# T-STorM32_motor_v251E-sq_Encoder.net
KiCad netlist of a schematic drawn in EAGLE
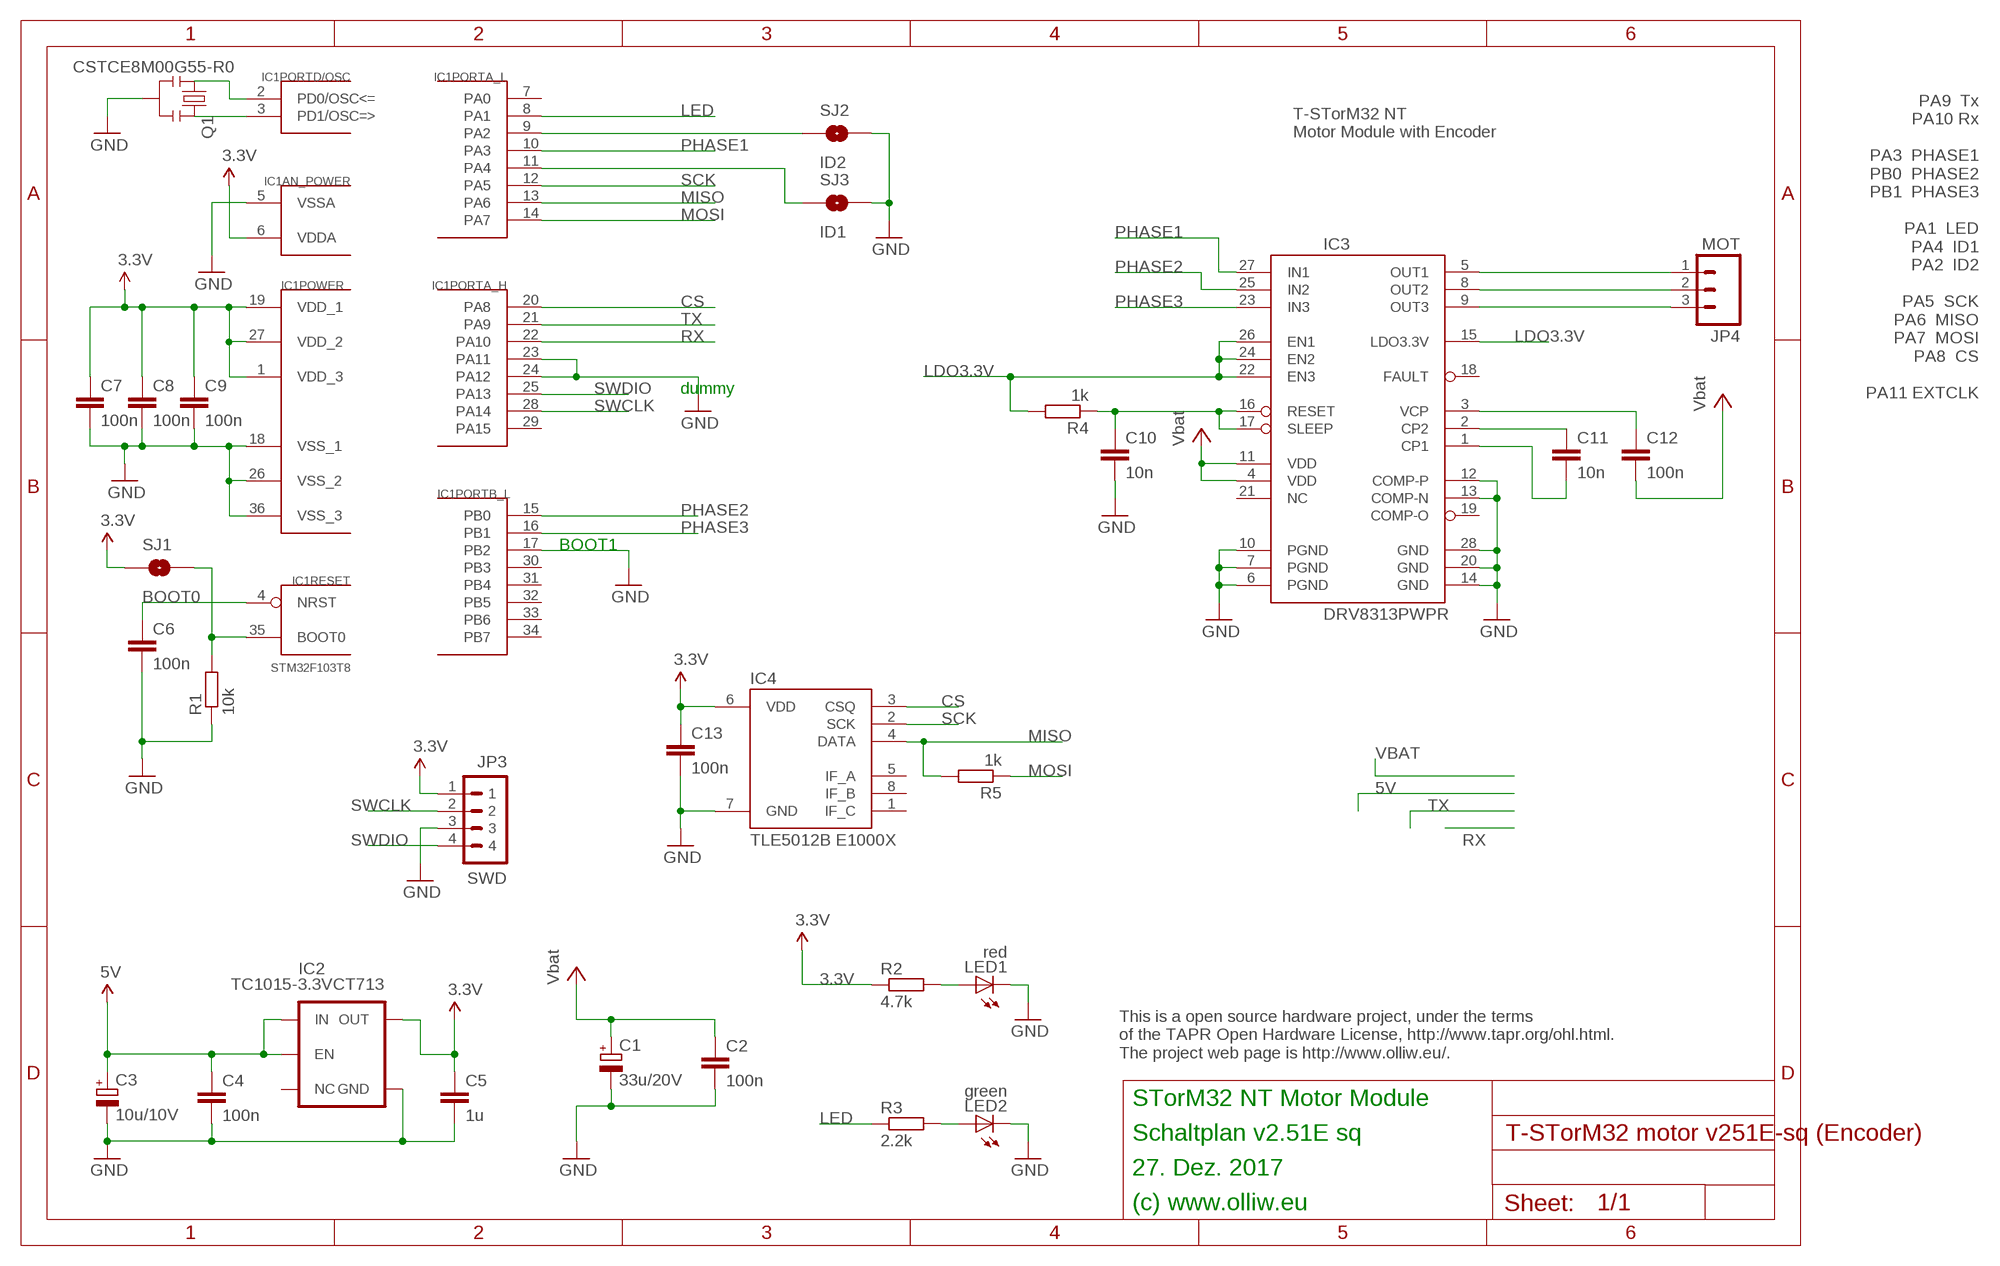
[diagram p0: schematic, sheet 1]

(export (version "E")
  (design (tool "Eeschema 10.0.6"))
  (components
    (comp (ref "C1")
      (value "33u/20V")
      (footprint "eagle-import:SMC_C")
      (libsource (lib "eagle-import") (part "CPOL-EUSMCC"))
    )
    (comp (ref "C2")
      (value "100n")
      (footprint "eagle-import:C0603")
      (libsource (lib "eagle-import") (part "C-EUC0603"))
    )
    (comp (ref "C3")
      (value "10u/10V")
      (footprint "eagle-import:SMC_B")
      (libsource (lib "eagle-import") (part "CPOL-EUSMCB"))
    )
    (comp (ref "C4")
      (value "100n")
      (footprint "eagle-import:C0603")
      (libsource (lib "eagle-import") (part "C-EUC0603"))
    )
    (comp (ref "C5")
      (value "1u")
      (footprint "eagle-import:C0603")
      (libsource (lib "eagle-import") (part "C-EUC0603"))
    )
    (comp (ref "C6")
      (value "100n")
      (footprint "eagle-import:C0603")
      (libsource (lib "eagle-import") (part "C-EUC0603"))
    )
    (comp (ref "C7")
      (value "100n")
      (footprint "eagle-import:C0603")
      (libsource (lib "eagle-import") (part "C-EUC0603"))
    )
    (comp (ref "C8")
      (value "100n")
      (footprint "eagle-import:C0603")
      (libsource (lib "eagle-import") (part "C-EUC0603"))
    )
    (comp (ref "C9")
      (value "100n")
      (footprint "eagle-import:C0603")
      (libsource (lib "eagle-import") (part "C-EUC0603"))
    )
    (comp (ref "C10")
      (value "10n")
      (footprint "eagle-import:C0603")
      (libsource (lib "eagle-import") (part "C-EUC0603"))
    )
    (comp (ref "C11")
      (value "10n")
      (footprint "eagle-import:C0603")
      (libsource (lib "eagle-import") (part "C-EUC0603"))
    )
    (comp (ref "C12")
      (value "100n")
      (footprint "eagle-import:C0603")
      (libsource (lib "eagle-import") (part "C-EUC0603"))
    )
    (comp (ref "C13")
      (value "100n")
      (footprint "eagle-import:C0603")
      (libsource (lib "eagle-import") (part "C-EUC0603"))
    )
    (comp (ref "IC1")
      (value "STM32F103T8")
      (footprint "eagle-import:VFQFPN36")
      (libsource (lib "eagle-import") (part "STM32F10XTXU6"))
    )
    (comp (ref "IC2")
      (value "TC1015-3.3VCT713")
      (footprint "eagle-import:SOT23-5")
      (libsource (lib "eagle-import") (part "V_REG_TPS76433SOT23-5"))
    )
    (comp (ref "IC3")
      (value "DRV8313PWPR")
      (footprint "eagle-import:HTSSOP28")
      (libsource (lib "eagle-import") (part "DRV8313"))
    )
    (comp (ref "IC4")
      (value "TLE5012B E1000X")
      (footprint "eagle-import:SO08")
      (libsource (lib "eagle-import") (part "TLE5012B"))
    )
    (comp (ref "JP3")
      (value "SWD")
      (footprint "eagle-import:4X1_1P27_OCT_BILEX")
      (libsource (lib "eagle-import") (part "P4X1_1P27-OCT_BILEX"))
    )
    (comp (ref "JP4")
      (value "MOT")
      (footprint "eagle-import:1X03_NO_SILK")
      (libsource (lib "eagle-import") (part "M031X03_NO_SILK"))
    )
    (comp (ref "LED1")
      (value "red")
      (footprint "eagle-import:CHIPLED_0603")
      (libsource (lib "eagle-import") (part "LEDCHIPLED_0603"))
    )
    (comp (ref "LED2")
      (value "green")
      (footprint "eagle-import:CHIPLED_0603")
      (libsource (lib "eagle-import") (part "LEDCHIPLED_0603"))
    )
    (comp (ref "Q1")
      (value "CSTCE8M00G55-R0")
      (footprint "eagle-import:RESONATOR-SMD")
      (libsource (lib "eagle-import") (part "RESONATORSMD"))
    )
    (comp (ref "R1")
      (value "10k")
      (footprint "eagle-import:R0603")
      (libsource (lib "eagle-import") (part "R-EU_R0603"))
    )
    (comp (ref "R2")
      (value "4.7k")
      (footprint "eagle-import:R0603")
      (libsource (lib "eagle-import") (part "R-EU_R0603"))
    )
    (comp (ref "R3")
      (value "2.2k")
      (footprint "eagle-import:R0603")
      (libsource (lib "eagle-import") (part "R-EU_R0603"))
    )
    (comp (ref "R4")
      (value "1k")
      (footprint "eagle-import:R0603")
      (libsource (lib "eagle-import") (part "R-EU_R0603"))
    )
    (comp (ref "R5")
      (value "1k")
      (footprint "eagle-import:R0603")
      (libsource (lib "eagle-import") (part "R-EU_R0603"))
    )
    (comp (ref "SJ1")
      (value "BOOT0")
      (footprint "eagle-import:SJ_2S-NO")
      (libsource (lib "eagle-import") (part "SOLDERJUMPERNO"))
    )
    (comp (ref "SJ2")
      (value "ID2")
      (footprint "eagle-import:SJ_2S-NO")
      (libsource (lib "eagle-import") (part "SOLDERJUMPERNO"))
    )
    (comp (ref "SJ3")
      (value "ID1")
      (footprint "eagle-import:SJ_2S-NO")
      (libsource (lib "eagle-import") (part "SOLDERJUMPERNO"))
    )
  )
  (nets
    (net (code "1") (name "/CS") (class "Default")
      (node (ref "IC1") (pin "20") (pinfunction "PA8_20") (pintype "bidirectional"))
      (node (ref "IC4") (pin "3") (pinfunction "CSQ_3") (pintype "input"))
    )
    (net (code "2") (name "/LDO3.3V") (class "Default")
      (node (ref "IC3") (pin "15") (pinfunction "LDO3.3V_15") (pintype "output"))
      (node (ref "IC3") (pin "22") (pinfunction "EN3_22") (pintype "input"))
      (node (ref "IC3") (pin "24") (pinfunction "EN2_24") (pintype "input"))
      (node (ref "IC3") (pin "26") (pinfunction "EN1_26") (pintype "input"))
      (node (ref "R4") (pin "2") (pinfunction "2_2") (pintype "passive"))
    )
    (net (code "3") (name "/LED") (class "Default")
      (node (ref "IC1") (pin "8") (pinfunction "PA1_8") (pintype "bidirectional"))
      (node (ref "R3") (pin "1") (pinfunction "1_1") (pintype "passive"))
    )
    (net (code "4") (name "/MISO") (class "Default")
      (node (ref "IC1") (pin "13") (pinfunction "PA6_13") (pintype "bidirectional"))
      (node (ref "IC4") (pin "4") (pinfunction "DATA_4") (pintype "bidirectional"))
      (node (ref "R5") (pin "2") (pinfunction "2_2") (pintype "passive"))
    )
    (net (code "5") (name "/MOSI") (class "Default")
      (node (ref "IC1") (pin "14") (pinfunction "PA7_14") (pintype "bidirectional"))
      (node (ref "R5") (pin "1") (pinfunction "1_1") (pintype "passive"))
    )
    (net (code "6") (name "/PHASE1") (class "Default")
      (node (ref "IC1") (pin "10") (pinfunction "PA3_10") (pintype "bidirectional"))
      (node (ref "IC3") (pin "27") (pinfunction "IN1_27") (pintype "input"))
    )
    (net (code "7") (name "/PHASE2") (class "Default")
      (node (ref "IC1") (pin "15") (pinfunction "PB0_15") (pintype "bidirectional"))
      (node (ref "IC3") (pin "25") (pinfunction "IN2_25") (pintype "input"))
    )
    (net (code "8") (name "/PHASE3") (class "Default")
      (node (ref "IC1") (pin "16") (pinfunction "PB1_16") (pintype "bidirectional"))
      (node (ref "IC3") (pin "23") (pinfunction "IN3_23") (pintype "input"))
    )
    (net (code "9") (name "/RX") (class "Default")
      (node (ref "IC1") (pin "22") (pinfunction "PA10_22") (pintype "bidirectional"))
    )
    (net (code "10") (name "/SCK") (class "Default")
      (node (ref "IC1") (pin "12") (pinfunction "PA5_12") (pintype "bidirectional"))
      (node (ref "IC4") (pin "2") (pinfunction "SCK_2") (pintype "input"))
    )
    (net (code "11") (name "/SWCLK") (class "Default")
      (node (ref "IC1") (pin "28") (pinfunction "PA14_28") (pintype "bidirectional"))
      (node (ref "JP3") (pin "2") (pinfunction "2_2") (pintype "passive"))
    )
    (net (code "12") (name "/SWDIO") (class "Default")
      (node (ref "IC1") (pin "25") (pinfunction "PA13_25") (pintype "bidirectional"))
      (node (ref "JP3") (pin "4") (pinfunction "4_4") (pintype "passive"))
    )
    (net (code "13") (name "/TX") (class "Default")
      (node (ref "IC1") (pin "21") (pinfunction "PA9_21") (pintype "bidirectional"))
    )
    (net (code "14") (name "3.3V") (class "Default")
      (node (ref "C13") (pin "1") (pinfunction "1_1") (pintype "passive"))
      (node (ref "C5") (pin "1") (pinfunction "1_1") (pintype "passive"))
      (node (ref "C7") (pin "1") (pinfunction "1_1") (pintype "passive"))
      (node (ref "C8") (pin "1") (pinfunction "1_1") (pintype "passive"))
      (node (ref "C9") (pin "1") (pinfunction "1_1") (pintype "passive"))
      (node (ref "IC1") (pin "1") (pinfunction "VDD_3_1") (pintype "power_in"))
      (node (ref "IC1") (pin "19") (pinfunction "VDD_1_19") (pintype "power_in"))
      (node (ref "IC1") (pin "27") (pinfunction "VDD_2_27") (pintype "power_in"))
      (node (ref "IC1") (pin "6") (pinfunction "VDDA_6") (pintype "power_in"))
      (node (ref "IC2") (pin "5") (pinfunction "OUT_5") (pintype "passive"))
      (node (ref "IC4") (pin "6") (pinfunction "VDD_6") (pintype "power_in"))
      (node (ref "JP3") (pin "1") (pinfunction "1_1") (pintype "passive"))
      (node (ref "R2") (pin "1") (pinfunction "1_1") (pintype "passive"))
      (node (ref "SJ1") (pin "1") (pinfunction "1_1") (pintype "passive"))
    )
    (net (code "15") (name "5V") (class "Default")
      (node (ref "C3") (pin "+") (pinfunction "+_+") (pintype "passive"))
      (node (ref "C4") (pin "1") (pinfunction "1_1") (pintype "passive"))
      (node (ref "IC2") (pin "1") (pinfunction "IN_1") (pintype "input"))
      (node (ref "IC2") (pin "3") (pinfunction "EN_3") (pintype "input"))
    )
    (net (code "16") (name "GND") (class "Default")
      (node (ref "C1") (pin "-") (pinfunction "-_-") (pintype "passive"))
      (node (ref "C10") (pin "2") (pinfunction "2_2") (pintype "passive"))
      (node (ref "C13") (pin "2") (pinfunction "2_2") (pintype "passive"))
      (node (ref "C2") (pin "2") (pinfunction "2_2") (pintype "passive"))
      (node (ref "C3") (pin "-") (pinfunction "-_-") (pintype "passive"))
      (node (ref "C4") (pin "2") (pinfunction "2_2") (pintype "passive"))
      (node (ref "C5") (pin "2") (pinfunction "2_2") (pintype "passive"))
      (node (ref "C6") (pin "2") (pinfunction "2_2") (pintype "passive"))
      (node (ref "C7") (pin "2") (pinfunction "2_2") (pintype "passive"))
      (node (ref "C8") (pin "2") (pinfunction "2_2") (pintype "passive"))
      (node (ref "C9") (pin "2") (pinfunction "2_2") (pintype "passive"))
      (node (ref "IC1") (pin "17") (pinfunction "PB2_17") (pintype "bidirectional"))
      (node (ref "IC1") (pin "18") (pinfunction "VSS_1_18") (pintype "power_in"))
      (node (ref "IC1") (pin "23") (pinfunction "PA11_23") (pintype "bidirectional"))
      (node (ref "IC1") (pin "24") (pinfunction "PA12_24") (pintype "bidirectional"))
      (node (ref "IC1") (pin "26") (pinfunction "VSS_2_26") (pintype "power_in"))
      (node (ref "IC1") (pin "36") (pinfunction "VSS_3_36") (pintype "power_in"))
      (node (ref "IC1") (pin "5") (pinfunction "VSSA_5") (pintype "power_in"))
      (node (ref "IC2") (pin "2") (pinfunction "GND_2") (pintype "input"))
      (node (ref "IC3") (pin "10") (pinfunction "PGND_10") (pintype "power_in"))
      (node (ref "IC3") (pin "12") (pinfunction "COMP-P_12") (pintype "input"))
      (node (ref "IC3") (pin "13") (pinfunction "COMP-N_13") (pintype "input"))
      (node (ref "IC3") (pin "14") (pinfunction "GND_14") (pintype "power_in"))
      (node (ref "IC3") (pin "20") (pinfunction "GND_20") (pintype "power_in"))
      (node (ref "IC3") (pin "28") (pinfunction "GND_28") (pintype "power_in"))
      (node (ref "IC3") (pin "6") (pinfunction "PGND_6") (pintype "power_in"))
      (node (ref "IC3") (pin "7") (pinfunction "PGND_7") (pintype "power_in"))
      (node (ref "IC4") (pin "7") (pinfunction "GND_7") (pintype "power_in"))
      (node (ref "JP3") (pin "3") (pinfunction "3_3") (pintype "passive"))
      (node (ref "LED1") (pin "C") (pinfunction "C_C") (pintype "passive"))
      (node (ref "LED2") (pin "C") (pinfunction "C_C") (pintype "passive"))
      (node (ref "Q1") (pin "2") (pinfunction "2_2") (pintype "passive"))
      (node (ref "R1") (pin "1") (pinfunction "1_1") (pintype "passive"))
      (node (ref "SJ2") (pin "2") (pinfunction "2_2") (pintype "passive"))
      (node (ref "SJ3") (pin "2") (pinfunction "2_2") (pintype "passive"))
    )
    (net (code "17") (name "Net-(IC1C-PA2)") (class "Default")
      (node (ref "IC1") (pin "9") (pinfunction "PA2_9") (pintype "bidirectional"))
      (node (ref "SJ2") (pin "1") (pinfunction "1_1") (pintype "passive"))
    )
    (net (code "18") (name "Net-(IC1C-PA4)") (class "Default")
      (node (ref "IC1") (pin "11") (pinfunction "PA4_11") (pintype "bidirectional"))
      (node (ref "SJ3") (pin "1") (pinfunction "1_1") (pintype "passive"))
    )
    (net (code "19") (name "Net-(IC1E-PD0{slash}OSC<=)") (class "Default")
      (node (ref "IC1") (pin "2") (pinfunction "PD0/OSC<=_2") (pintype "bidirectional"))
      (node (ref "Q1") (pin "1") (pinfunction "1_1") (pintype "passive"))
    )
    (net (code "20") (name "Net-(IC1E-PD1{slash}OSC=>)") (class "Default")
      (node (ref "IC1") (pin "3") (pinfunction "PD1/OSC=>_3") (pintype "bidirectional"))
      (node (ref "Q1") (pin "3") (pinfunction "3_3") (pintype "passive"))
    )
    (net (code "21") (name "Net-(IC1G-BOOT0)") (class "Default")
      (node (ref "IC1") (pin "35") (pinfunction "BOOT0_35") (pintype "input"))
      (node (ref "R1") (pin "2") (pinfunction "2_2") (pintype "passive"))
      (node (ref "SJ1") (pin "2") (pinfunction "2_2") (pintype "passive"))
    )
    (net (code "22") (name "Net-(IC1G-NRST)") (class "Default")
      (node (ref "C6") (pin "1") (pinfunction "1_1") (pintype "passive"))
      (node (ref "IC1") (pin "4") (pinfunction "NRST_4") (pintype "input"))
    )
    (net (code "23") (name "Net-(IC3-CP1)") (class "Default")
      (node (ref "C11") (pin "2") (pinfunction "2_2") (pintype "passive"))
      (node (ref "IC3") (pin "1") (pinfunction "CP1_1") (pintype "bidirectional"))
    )
    (net (code "24") (name "Net-(IC3-CP2)") (class "Default")
      (node (ref "C11") (pin "1") (pinfunction "1_1") (pintype "passive"))
      (node (ref "IC3") (pin "2") (pinfunction "CP2_2") (pintype "bidirectional"))
    )
    (net (code "25") (name "Net-(IC3-OUT1)") (class "Default")
      (node (ref "IC3") (pin "5") (pinfunction "OUT1_5") (pintype "output"))
      (node (ref "JP4") (pin "1") (pinfunction "1_1") (pintype "passive"))
    )
    (net (code "26") (name "Net-(IC3-OUT2)") (class "Default")
      (node (ref "IC3") (pin "8") (pinfunction "OUT2_8") (pintype "output"))
      (node (ref "JP4") (pin "2") (pinfunction "2_2") (pintype "passive"))
    )
    (net (code "27") (name "Net-(IC3-OUT3)") (class "Default")
      (node (ref "IC3") (pin "9") (pinfunction "OUT3_9") (pintype "output"))
      (node (ref "JP4") (pin "3") (pinfunction "3_3") (pintype "passive"))
    )
    (net (code "28") (name "Net-(IC3-RESET)") (class "Default")
      (node (ref "C10") (pin "1") (pinfunction "1_1") (pintype "passive"))
      (node (ref "IC3") (pin "16") (pinfunction "RESET_16") (pintype "input"))
      (node (ref "IC3") (pin "17") (pinfunction "SLEEP_17") (pintype "input"))
      (node (ref "R4") (pin "1") (pinfunction "1_1") (pintype "passive"))
    )
    (net (code "29") (name "Net-(IC3-VCP)") (class "Default")
      (node (ref "C12") (pin "1") (pinfunction "1_1") (pintype "passive"))
      (node (ref "IC3") (pin "3") (pinfunction "VCP_3") (pintype "bidirectional"))
    )
    (net (code "30") (name "Net-(LED1-PadA)") (class "Default")
      (node (ref "LED1") (pin "A") (pinfunction "A_A") (pintype "passive"))
      (node (ref "R2") (pin "2") (pinfunction "2_2") (pintype "passive"))
    )
    (net (code "31") (name "Net-(LED2-PadA)") (class "Default")
      (node (ref "LED2") (pin "A") (pinfunction "A_A") (pintype "passive"))
      (node (ref "R3") (pin "2") (pinfunction "2_2") (pintype "passive"))
    )
    (net (code "32") (name "Vbat") (class "Default")
      (node (ref "C1") (pin "+") (pinfunction "+_+") (pintype "passive"))
      (node (ref "C12") (pin "2") (pinfunction "2_2") (pintype "passive"))
      (node (ref "C2") (pin "1") (pinfunction "1_1") (pintype "passive"))
      (node (ref "IC3") (pin "11") (pinfunction "VDD_11") (pintype "power_in"))
      (node (ref "IC3") (pin "4") (pinfunction "VDD_4") (pintype "power_in"))
    )
    (net (code "33") (name "unconnected-(IC1B-PA15-Pad29)") (class "Default")
      (node (ref "IC1") (pin "29") (pinfunction "PA15_29") (pintype "bidirectional"))
    )
    (net (code "34") (name "unconnected-(IC1C-PA0-Pad7)") (class "Default")
      (node (ref "IC1") (pin "7") (pinfunction "PA0_7") (pintype "bidirectional"))
    )
    (net (code "35") (name "unconnected-(IC1D-PB3-Pad30)") (class "Default")
      (node (ref "IC1") (pin "30") (pinfunction "PB3_30") (pintype "bidirectional"))
    )
    (net (code "36") (name "unconnected-(IC1D-PB4-Pad31)") (class "Default")
      (node (ref "IC1") (pin "31") (pinfunction "PB4_31") (pintype "bidirectional"))
    )
    (net (code "37") (name "unconnected-(IC1D-PB5-Pad32)") (class "Default")
      (node (ref "IC1") (pin "32") (pinfunction "PB5_32") (pintype "bidirectional"))
    )
    (net (code "38") (name "unconnected-(IC1D-PB6-Pad33)") (class "Default")
      (node (ref "IC1") (pin "33") (pinfunction "PB6_33") (pintype "bidirectional"))
    )
    (net (code "39") (name "unconnected-(IC1D-PB7-Pad34)") (class "Default")
      (node (ref "IC1") (pin "34") (pinfunction "PB7_34") (pintype "bidirectional"))
    )
    (net (code "40") (name "unconnected-(IC2-NC-Pad4)") (class "Default")
      (node (ref "IC2") (pin "4") (pinfunction "NC_4") (pintype "input"))
    )
    (net (code "41") (name "unconnected-(IC3-COMP-O-Pad19)") (class "Default")
      (node (ref "IC3") (pin "19") (pinfunction "COMP-O_19") (pintype "output"))
    )
    (net (code "42") (name "unconnected-(IC3-FAULT-Pad18)") (class "Default")
      (node (ref "IC3") (pin "18") (pinfunction "FAULT_18") (pintype "output"))
    )
    (net (code "43") (name "unconnected-(IC3-NC-Pad21)") (class "Default")
      (node (ref "IC3") (pin "21") (pinfunction "NC_21") (pintype "no_connect"))
    )
    (net (code "44") (name "unconnected-(IC4-IF_A-Pad5)") (class "Default")
      (node (ref "IC4") (pin "5") (pinfunction "IF_A_5") (pintype "bidirectional"))
    )
    (net (code "45") (name "unconnected-(IC4-IF_B-Pad8)") (class "Default")
      (node (ref "IC4") (pin "8") (pinfunction "IF_B_8") (pintype "output"))
    )
    (net (code "46") (name "unconnected-(IC4-IF_C-Pad1)") (class "Default")
      (node (ref "IC4") (pin "1") (pinfunction "IF_C_1") (pintype "bidirectional"))
    )
  )
)
